# Industrial-Controller_Relay.net
KiCad netlist of a schematic drawn in Altium Designer
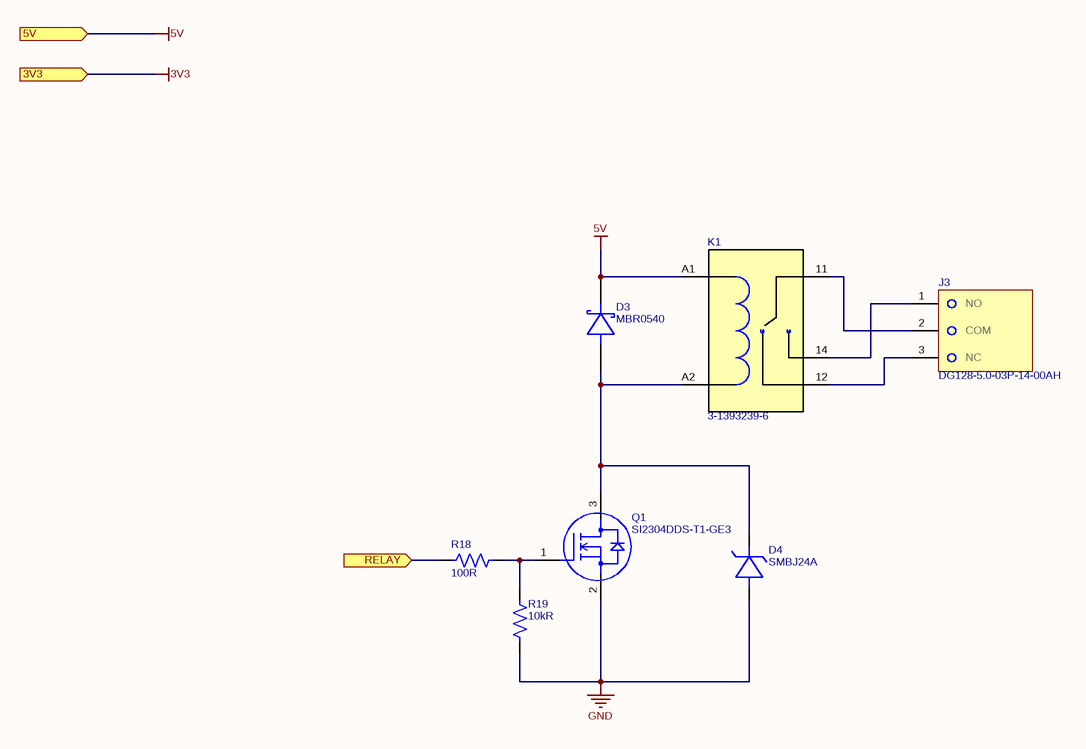
[diagram p0: Industrial-Controller_Relay.SchDoc]

(export (version "E")
  (design (tool "Eeschema 10.0.6"))
  (components
    (comp (ref "D3")
      (value "MBR0540")
      (footprint "SOD-123")
      (description "DIODE SCHOTTKY 40V 500MA SOD123")
      (fields (field (name "MANUFACTURER") "ON Semiconductor / Fairchild"))
      (libsource (lib "Industrial-Controller") (part "MBR0540"))
    )
    (comp (ref "D4")
      (value "SMBJ24A")
      (footprint "SMB")
      (description "TVS DIODE 24VWM 38.9VC SMB")
      (libsource (lib "Industrial-Controller") (part "SMBJ24A"))
    )
    (comp (ref "J3")
      (value "DG128-5.0-03P-14-00AH")
      (footprint "DG128-5.0-03P-14")
      (description "TERM BLK 3P TOP ENTRY 5MM SMD")
      (libsource (lib "Industrial-Controller") (part "DG128-5.0-03P-14"))
    )
    (comp (ref "K1")
      (value "3-1393239-6")
      (footprint "3-1393239-6")
      (description "RELAY GEN PURPOSE SPDT 10A 5V")
      (libsource (lib "Industrial-Controller") (part "3-1393239-6"))
    )
    (comp (ref "Q1")
      (value "SI2304DDS-T1-GE3")
      (footprint "SOT-23-3")
      (description "MOSFET N-CH 30V 3.3A/3.6A SOT23")
      (libsource (lib "Industrial-Controller") (part "SI2304DDS-T1-GE3"))
    )
    (comp (ref "R18")
      (value "100R")
      (footprint "RES_0603")
      (description "RES 100 OHM 1% 1/10W 0603")
      (fields (field (name "TOLERANCE") "1%"))
      (libsource (lib "Industrial-Controller") (part "RC0603FR-07100RL"))
    )
    (comp (ref "R19")
      (value "10kR")
      (footprint "RES_0603")
      (description "RES 10K OHM 1% 1/10W 0603")
      (fields (field (name "TOLERANCE") "1%"))
      (libsource (lib "Industrial-Controller") (part "RC0603FR-0710KL"))
    )
  )
  (nets
    (net (code "1") (name "/RELAY") (class "Default")
      (node (ref "R18") (pin "1") (pinfunction "1_1") (pintype "passive"))
    )
    (net (code "3") (name "5V") (class "Default")
      (node (ref "D3") (pin "1") (pinfunction "C_1") (pintype "passive"))
      (node (ref "K1") (pin "A1") (pinfunction "A1_A1") (pintype "passive"))
    )
    (net (code "4") (name "GND") (class "Default")
      (node (ref "D4") (pin "2") (pinfunction "A_2") (pintype "passive"))
      (node (ref "Q1") (pin "2") (pinfunction "S_2") (pintype "passive"))
      (node (ref "R19") (pin "2") (pinfunction "2_2") (pintype "passive"))
    )
    (net (code "5") (name "Net-(D3-A)") (class "Default")
      (node (ref "D3") (pin "2") (pinfunction "A_2") (pintype "passive"))
      (node (ref "D4") (pin "1") (pinfunction "C_1") (pintype "passive"))
      (node (ref "K1") (pin "A2") (pinfunction "A2_A2") (pintype "passive"))
      (node (ref "Q1") (pin "3") (pinfunction "D_3") (pintype "passive"))
    )
    (net (code "6") (name "Net-(K1-COM)") (class "Default")
      (node (ref "J3") (pin "2") (pinfunction "2_2") (pintype "passive"))
      (node (ref "K1") (pin "11") (pinfunction "COM_11") (pintype "passive"))
    )
    (net (code "7") (name "Net-(K1-NC)") (class "Default")
      (node (ref "J3") (pin "3") (pinfunction "3_3") (pintype "passive"))
      (node (ref "K1") (pin "12") (pinfunction "NC_12") (pintype "passive"))
    )
    (net (code "8") (name "Net-(K1-NO)") (class "Default")
      (node (ref "J3") (pin "1") (pinfunction "1_1") (pintype "passive"))
      (node (ref "K1") (pin "14") (pinfunction "NO_14") (pintype "passive"))
    )
    (net (code "9") (name "Net-(Q1-G)") (class "Default")
      (node (ref "Q1") (pin "1") (pinfunction "G_1") (pintype "passive"))
      (node (ref "R18") (pin "2") (pinfunction "2_2") (pintype "passive"))
      (node (ref "R19") (pin "1") (pinfunction "1_1") (pintype "passive"))
    )
  )
)
